# stm32f030f4_qc_trigger.net
KiCad netlist of a schematic drawn in EAGLE
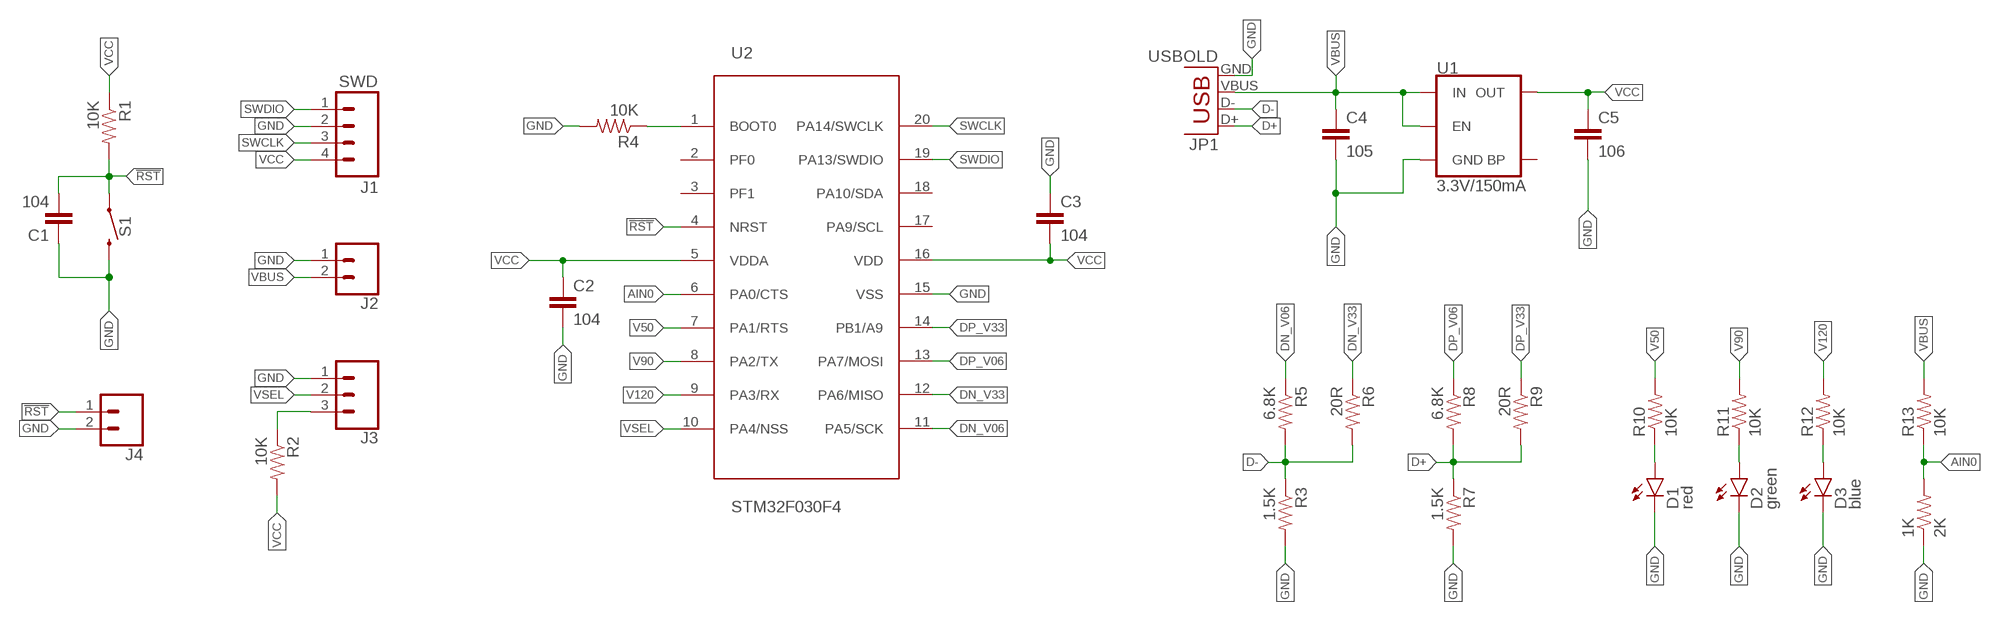
[diagram p0: schematic, sheet 1]

(export (version "E")
  (design (tool "Eeschema 10.0.6"))
  (components
    (comp (ref "1K")
      (value "2K")
      (footprint "eagle-import:0402-RES")
      (libsource (lib "eagle-import") (part "RESISTOR0402"))
    )
    (comp (ref "C1")
      (value "104")
      (footprint "eagle-import:0402-CAP")
      (libsource (lib "eagle-import") (part "CAP0402-CAP"))
    )
    (comp (ref "C2")
      (value "104")
      (footprint "eagle-import:0402-CAP")
      (libsource (lib "eagle-import") (part "CAP0402-CAP"))
    )
    (comp (ref "C3")
      (value "104")
      (footprint "eagle-import:0402-CAP")
      (libsource (lib "eagle-import") (part "CAP0402-CAP"))
    )
    (comp (ref "C4")
      (value "105")
      (footprint "eagle-import:0603-CAP")
      (libsource (lib "eagle-import") (part "CAP0603-CAP"))
    )
    (comp (ref "C5")
      (value "106")
      (footprint "eagle-import:0402-CAP")
      (libsource (lib "eagle-import") (part "CAP0402-CAP"))
    )
    (comp (ref "D1")
      (value "red")
      (footprint "eagle-import:LED-0603-EASY")
      (libsource (lib "eagle-import") (part "LED-EASY"))
    )
    (comp (ref "D2")
      (value "green")
      (footprint "eagle-import:LED-0603-EASY")
      (libsource (lib "eagle-import") (part "LED-EASY"))
    )
    (comp (ref "D3")
      (value "blue")
      (footprint "eagle-import:LED-0603-EASY")
      (libsource (lib "eagle-import") (part "LED-EASY"))
    )
    (comp (ref "J1")
      (value "SWD")
      (footprint "eagle-import:1X04_NO_SILK")
      (libsource (lib "eagle-import") (part "M041X04_NO_SILK"))
    )
    (comp (ref "J2")
      (value "CONN_025MM")
      (footprint "eagle-import:SCREWTERMINAL-5MM-2")
      (libsource (lib "eagle-import") (part "CONN_025MM"))
    )
    (comp (ref "J3")
      (value "CONN_031X03_NO_SILK")
      (footprint "eagle-import:1X03_NO_SILK")
      (libsource (lib "eagle-import") (part "CONN_031X03_NO_SILK"))
    )
    (comp (ref "J4")
      (value "CONN_021X02_NO_SILK")
      (footprint "eagle-import:1X02_NO_SILK")
      (libsource (lib "eagle-import") (part "CONN_021X02_NO_SILK"))
    )
    (comp (ref "JP1")
      (value "USBOLD")
      (footprint "eagle-import:USB-MINIB-OLD")
      (libsource (lib "eagle-import") (part "USBOLD"))
    )
    (comp (ref "R1")
      (value "10K")
      (footprint "eagle-import:0402-RES")
      (libsource (lib "eagle-import") (part "RESISTOR0402"))
    )
    (comp (ref "R2")
      (value "10K")
      (footprint "eagle-import:0402-RES")
      (libsource (lib "eagle-import") (part "RESISTOR0402"))
    )
    (comp (ref "R3")
      (value "1.5K")
      (footprint "eagle-import:0402-RES")
      (libsource (lib "eagle-import") (part "RESISTOR0402"))
    )
    (comp (ref "R4")
      (value "10K")
      (footprint "eagle-import:0402-RES")
      (libsource (lib "eagle-import") (part "RESISTOR0402"))
    )
    (comp (ref "R5")
      (value "6.8K")
      (footprint "eagle-import:0402-RES")
      (libsource (lib "eagle-import") (part "RESISTOR0402"))
    )
    (comp (ref "R6")
      (value "20R")
      (footprint "eagle-import:0402-RES")
      (libsource (lib "eagle-import") (part "RESISTOR0402"))
    )
    (comp (ref "R7")
      (value "1.5K")
      (footprint "eagle-import:0402-RES")
      (libsource (lib "eagle-import") (part "RESISTOR0402"))
    )
    (comp (ref "R8")
      (value "6.8K")
      (footprint "eagle-import:0402-RES")
      (libsource (lib "eagle-import") (part "RESISTOR0402"))
    )
    (comp (ref "R9")
      (value "20R")
      (footprint "eagle-import:0402-RES")
      (libsource (lib "eagle-import") (part "RESISTOR0402"))
    )
    (comp (ref "R10")
      (value "10K")
      (footprint "eagle-import:0402-RES")
      (libsource (lib "eagle-import") (part "RESISTOR0402"))
    )
    (comp (ref "R11")
      (value "10K")
      (footprint "eagle-import:0402-RES")
      (libsource (lib "eagle-import") (part "RESISTOR0402"))
    )
    (comp (ref "R12")
      (value "10K")
      (footprint "eagle-import:0402-RES")
      (libsource (lib "eagle-import") (part "RESISTOR0402"))
    )
    (comp (ref "R13")
      (value "10K")
      (footprint "eagle-import:0402-RES")
      (libsource (lib "eagle-import") (part "RESISTOR0402"))
    )
    (comp (ref "S1")
      (value "MOMENTARY-SWITCH-SPST-PTH-6.0MM")
      (footprint "eagle-import:TACTILE_SWITCH_PTH_6.0MM")
      (libsource (lib "eagle-import") (part "MOMENTARY-SWITCH-SPST-PTH-6.0MM"))
    )
    (comp (ref "U1")
      (value "3.3V/150mA")
      (footprint "eagle-import:SOT23-5")
      (libsource (lib "eagle-import") (part "V_REG_MIC52053.3V"))
    )
    (comp (ref "U2")
      (value "STM32F030F4")
      (footprint "eagle-import:TSSOP20")
      (libsource (lib "eagle-import") (part "STM32F030F4"))
    )
  )
  (nets
    (net (code "1") (name "/~{RST}") (class "Default")
      (node (ref "C1") (pin "2") (pinfunction "2_2") (pintype "passive"))
      (node (ref "J4") (pin "1") (pinfunction "1_1") (pintype "passive"))
      (node (ref "R1") (pin "2") (pinfunction "2_2") (pintype "passive"))
      (node (ref "S1") (pin "1") (pinfunction "1_1") (pintype "passive"))
      (node (ref "U2") (pin "4") (pinfunction "NRST_4") (pintype "bidirectional"))
    )
    (net (code "2") (name "AIN0") (class "Default")
      (node (ref "1K") (pin "2") (pinfunction "2_2") (pintype "passive"))
      (node (ref "R13") (pin "1") (pinfunction "1_1") (pintype "passive"))
      (node (ref "U2") (pin "6") (pinfunction "PA0/CTS_6") (pintype "bidirectional"))
    )
    (net (code "3") (name "D+") (class "Default")
      (node (ref "JP1") (pin "D+") (pinfunction "D+_D+") (pintype "bidirectional"))
      (node (ref "R7") (pin "1") (pinfunction "1_1") (pintype "passive"))
      (node (ref "R8") (pin "2") (pinfunction "2_2") (pintype "passive"))
      (node (ref "R9") (pin "2") (pinfunction "2_2") (pintype "passive"))
    )
    (net (code "4") (name "D-") (class "Default")
      (node (ref "JP1") (pin "D-") (pinfunction "D-_D-") (pintype "bidirectional"))
      (node (ref "R3") (pin "1") (pinfunction "1_1") (pintype "passive"))
      (node (ref "R5") (pin "2") (pinfunction "2_2") (pintype "passive"))
      (node (ref "R6") (pin "2") (pinfunction "2_2") (pintype "passive"))
    )
    (net (code "5") (name "DN_V06") (class "Default")
      (node (ref "R5") (pin "1") (pinfunction "1_1") (pintype "passive"))
      (node (ref "U2") (pin "11") (pinfunction "PA5/SCK_11") (pintype "bidirectional"))
    )
    (net (code "6") (name "DN_V33") (class "Default")
      (node (ref "R6") (pin "1") (pinfunction "1_1") (pintype "passive"))
      (node (ref "U2") (pin "12") (pinfunction "PA6/MISO_12") (pintype "bidirectional"))
    )
    (net (code "7") (name "DP_V06") (class "Default")
      (node (ref "R8") (pin "1") (pinfunction "1_1") (pintype "passive"))
      (node (ref "U2") (pin "13") (pinfunction "PA7/MOSI_13") (pintype "bidirectional"))
    )
    (net (code "8") (name "DP_V33") (class "Default")
      (node (ref "R9") (pin "1") (pinfunction "1_1") (pintype "passive"))
      (node (ref "U2") (pin "14") (pinfunction "PB1/A9_14") (pintype "bidirectional"))
    )
    (net (code "9") (name "GND") (class "Default")
      (node (ref "1K") (pin "1") (pinfunction "1_1") (pintype "passive"))
      (node (ref "C1") (pin "1") (pinfunction "1_1") (pintype "passive"))
      (node (ref "C2") (pin "2") (pinfunction "2_2") (pintype "passive"))
      (node (ref "C3") (pin "1") (pinfunction "1_1") (pintype "passive"))
      (node (ref "C4") (pin "2") (pinfunction "2_2") (pintype "passive"))
      (node (ref "C5") (pin "2") (pinfunction "2_2") (pintype "passive"))
      (node (ref "D1") (pin "-") (pinfunction "C_-") (pintype "passive"))
      (node (ref "D2") (pin "-") (pinfunction "C_-") (pintype "passive"))
      (node (ref "D3") (pin "-") (pinfunction "C_-") (pintype "passive"))
      (node (ref "J1") (pin "2") (pinfunction "2_2") (pintype "passive"))
      (node (ref "J2") (pin "1") (pinfunction "1_1") (pintype "passive"))
      (node (ref "J3") (pin "1") (pinfunction "1_1") (pintype "passive"))
      (node (ref "J4") (pin "2") (pinfunction "2_2") (pintype "passive"))
      (node (ref "JP1") (pin "GND") (pinfunction "GND_GND") (pintype "bidirectional"))
      (node (ref "R3") (pin "2") (pinfunction "2_2") (pintype "passive"))
      (node (ref "R4") (pin "2") (pinfunction "2_2") (pintype "passive"))
      (node (ref "R7") (pin "2") (pinfunction "2_2") (pintype "passive"))
      (node (ref "S1") (pin "3") (pinfunction "2_3") (pintype "passive"))
      (node (ref "U1") (pin "2") (pinfunction "GND_2") (pintype "input"))
      (node (ref "U2") (pin "15") (pinfunction "VSS_15") (pintype "bidirectional"))
    )
    (net (code "10") (name "Net-(D1-A)") (class "Default")
      (node (ref "D1") (pin "+") (pinfunction "A_+") (pintype "passive"))
      (node (ref "R10") (pin "1") (pinfunction "1_1") (pintype "passive"))
    )
    (net (code "11") (name "Net-(D2-A)") (class "Default")
      (node (ref "D2") (pin "+") (pinfunction "A_+") (pintype "passive"))
      (node (ref "R11") (pin "1") (pinfunction "1_1") (pintype "passive"))
    )
    (net (code "12") (name "Net-(D3-A)") (class "Default")
      (node (ref "D3") (pin "+") (pinfunction "A_+") (pintype "passive"))
      (node (ref "R12") (pin "1") (pinfunction "1_1") (pintype "passive"))
    )
    (net (code "13") (name "Net-(J3-Pad3)") (class "Default")
      (node (ref "J3") (pin "3") (pinfunction "3_3") (pintype "passive"))
      (node (ref "R2") (pin "1") (pinfunction "1_1") (pintype "passive"))
    )
    (net (code "14") (name "Net-(U2-BOOT0)") (class "Default")
      (node (ref "R4") (pin "1") (pinfunction "1_1") (pintype "passive"))
      (node (ref "U2") (pin "1") (pinfunction "BOOT0_1") (pintype "bidirectional"))
    )
    (net (code "15") (name "SWCLK") (class "Default")
      (node (ref "J1") (pin "3") (pinfunction "3_3") (pintype "passive"))
      (node (ref "U2") (pin "20") (pinfunction "PA14/SWCLK_20") (pintype "bidirectional"))
    )
    (net (code "16") (name "SWDIO") (class "Default")
      (node (ref "J1") (pin "1") (pinfunction "1_1") (pintype "passive"))
      (node (ref "U2") (pin "19") (pinfunction "PA13/SWDIO_19") (pintype "bidirectional"))
    )
    (net (code "17") (name "V50") (class "Default")
      (node (ref "R10") (pin "2") (pinfunction "2_2") (pintype "passive"))
      (node (ref "U2") (pin "7") (pinfunction "PA1/RTS_7") (pintype "bidirectional"))
    )
    (net (code "18") (name "V90") (class "Default")
      (node (ref "R11") (pin "2") (pinfunction "2_2") (pintype "passive"))
      (node (ref "U2") (pin "8") (pinfunction "PA2/TX_8") (pintype "bidirectional"))
    )
    (net (code "19") (name "V120") (class "Default")
      (node (ref "R12") (pin "2") (pinfunction "2_2") (pintype "passive"))
      (node (ref "U2") (pin "9") (pinfunction "PA3/RX_9") (pintype "bidirectional"))
    )
    (net (code "20") (name "VBUS") (class "Default")
      (node (ref "C4") (pin "1") (pinfunction "1_1") (pintype "passive"))
      (node (ref "J2") (pin "2") (pinfunction "2_2") (pintype "passive"))
      (node (ref "JP1") (pin "VBUS") (pinfunction "VBUS_VBUS") (pintype "bidirectional"))
      (node (ref "R13") (pin "2") (pinfunction "2_2") (pintype "passive"))
      (node (ref "U1") (pin "1") (pinfunction "IN_1") (pintype "input"))
      (node (ref "U1") (pin "3") (pinfunction "EN_3") (pintype "input"))
    )
    (net (code "21") (name "VCC") (class "Default")
      (node (ref "C2") (pin "1") (pinfunction "1_1") (pintype "passive"))
      (node (ref "C3") (pin "2") (pinfunction "2_2") (pintype "passive"))
      (node (ref "C5") (pin "1") (pinfunction "1_1") (pintype "passive"))
      (node (ref "J1") (pin "4") (pinfunction "4_4") (pintype "passive"))
      (node (ref "R1") (pin "1") (pinfunction "1_1") (pintype "passive"))
      (node (ref "R2") (pin "2") (pinfunction "2_2") (pintype "passive"))
      (node (ref "U1") (pin "5") (pinfunction "OUT_5") (pintype "passive"))
      (node (ref "U2") (pin "16") (pinfunction "VDD_16") (pintype "bidirectional"))
      (node (ref "U2") (pin "5") (pinfunction "VDDA_5") (pintype "bidirectional"))
    )
    (net (code "22") (name "VSEL") (class "Default")
      (node (ref "J3") (pin "2") (pinfunction "2_2") (pintype "passive"))
      (node (ref "U2") (pin "10") (pinfunction "PA4/NSS_10") (pintype "bidirectional"))
    )
    (net (code "23") (name "unconnected-(U1-BP-Pad4)") (class "Default")
      (node (ref "U1") (pin "4") (pinfunction "BP_4") (pintype "input"))
    )
    (net (code "24") (name "unconnected-(U2-PA9{slash}SCL-Pad17)") (class "Default")
      (node (ref "U2") (pin "17") (pinfunction "PA9/SCL_17") (pintype "bidirectional"))
    )
    (net (code "25") (name "unconnected-(U2-PA10{slash}SDA-Pad18)") (class "Default")
      (node (ref "U2") (pin "18") (pinfunction "PA10/SDA_18") (pintype "bidirectional"))
    )
    (net (code "26") (name "unconnected-(U2-PF0-Pad2)") (class "Default")
      (node (ref "U2") (pin "2") (pinfunction "PF0_2") (pintype "bidirectional"))
    )
    (net (code "27") (name "unconnected-(U2-PF1-Pad3)") (class "Default")
      (node (ref "U2") (pin "3") (pinfunction "PF1_3") (pintype "bidirectional"))
    )
  )
)
